# 03_-_BLOCK_DIAGRAM.net
KiCad netlist of a schematic drawn in Altium Designer
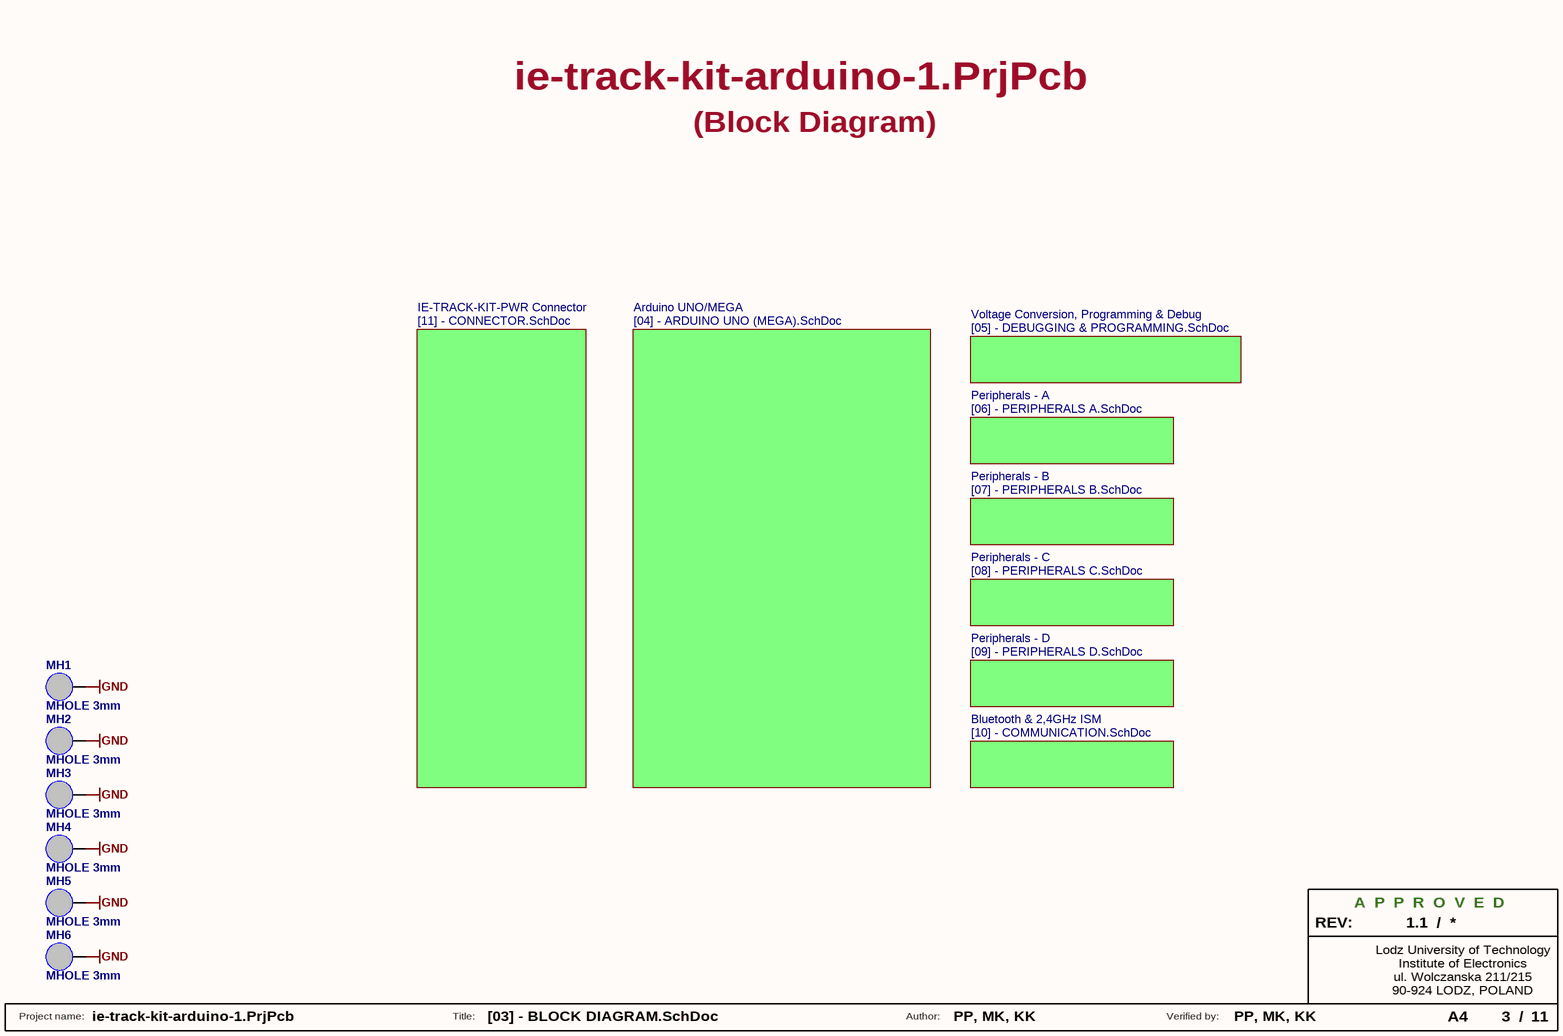
[diagram p0: [03] - BLOCK DIAGRAM.SchDoc]

(export (version "E")
  (design (tool "Eeschema 10.0.6"))
  (components
    (comp (ref "MH1")
      (value "MHOLE 3mm")
      (footprint "3mm screw drill I")
      (description "3mm Mounting Hole")
      (libsource (lib "mechanical_other") (part "MHOLE_3MM"))
    )
    (comp (ref "MH2")
      (value "MHOLE 3mm")
      (footprint "3mm screw drill I")
      (description "3mm Mounting Hole")
      (libsource (lib "mechanical_other") (part "MHOLE_3MM"))
    )
    (comp (ref "MH3")
      (value "MHOLE 3mm")
      (footprint "3mm screw drill I")
      (description "3mm Mounting Hole")
      (libsource (lib "mechanical_other") (part "MHOLE_3MM"))
    )
    (comp (ref "MH4")
      (value "MHOLE 3mm")
      (footprint "3mm screw drill I")
      (description "3mm Mounting Hole")
      (libsource (lib "mechanical_other") (part "MHOLE_3MM"))
    )
    (comp (ref "MH5")
      (value "MHOLE 3mm")
      (footprint "3mm screw drill I")
      (description "3mm Mounting Hole")
      (libsource (lib "mechanical_other") (part "MHOLE_3MM"))
    )
    (comp (ref "MH6")
      (value "MHOLE 3mm")
      (footprint "3mm screw drill I")
      (description "3mm Mounting Hole")
      (libsource (lib "mechanical_other") (part "MHOLE_3MM"))
    )
  )
  (nets
    (net (code "1") (name "GND") (class "Default")
      (node (ref "MH1") (pin "1") (pinfunction "GND_1") (pintype "passive"))
      (node (ref "MH2") (pin "1") (pinfunction "GND_1") (pintype "passive"))
      (node (ref "MH3") (pin "1") (pinfunction "GND_1") (pintype "passive"))
      (node (ref "MH4") (pin "1") (pinfunction "GND_1") (pintype "passive"))
      (node (ref "MH5") (pin "1") (pinfunction "GND_1") (pintype "passive"))
      (node (ref "MH6") (pin "1") (pinfunction "GND_1") (pintype "passive"))
    )
  )
)
